# WaterLevel.net
KiCad netlist of a schematic drawn in EAGLE
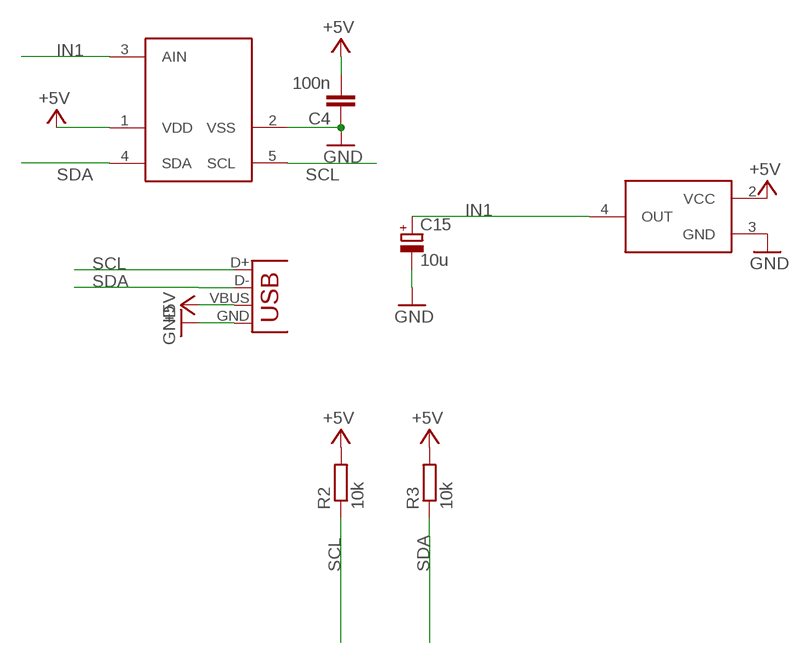
[diagram p0: schematic, sheet 1]

(export (version "E")
  (design (tool "Eeschema 10.0.6"))
  (components
    (comp (ref "C4")
      (value "100n")
      (footprint "eagle-import:C0805K")
      (libsource (lib "eagle-import") (part "C-EUC0805K"))
    )
    (comp (ref "C15")
      (value "10u")
      (footprint "eagle-import:A_3216-18W")
      (libsource (lib "eagle-import") (part "CPOL-EUA/3216-18W"))
    )
    (comp (ref "IC1")
      (value "MPVZ5004GW7U")
      (footprint "eagle-import:MPVZ5004GW7U")
      (libsource (lib "eagle-import") (part "MPVZ5004GW7U"))
    )
    (comp (ref "R2")
      (value "10k")
      (footprint "eagle-import:R0805")
      (libsource (lib "eagle-import") (part "R-EU_R0805"))
    )
    (comp (ref "R3")
      (value "10k")
      (footprint "eagle-import:R0805")
      (libsource (lib "eagle-import") (part "R-EU_R0805"))
    )
    (comp (ref "U$2")
      (value "MCP3221A7")
      (footprint "eagle-import:SOT23-5")
      (libsource (lib "eagle-import") (part "MCP3221"))
    )
    (comp (ref "X5")
      (value "USBSMD")
      (footprint "eagle-import:USB-MINIB")
      (libsource (lib "eagle-import") (part "USBSMD"))
    )
  )
  (nets
    (net (code "1") (name "+5V") (class "Default")
      (node (ref "C4") (pin "2") (pinfunction "2_2") (pintype "passive"))
      (node (ref "IC1") (pin "2") (pinfunction "VCC_2") (pintype "bidirectional"))
      (node (ref "R2") (pin "2") (pinfunction "2_2") (pintype "passive"))
      (node (ref "R3") (pin "2") (pinfunction "2_2") (pintype "passive"))
      (node (ref "U$2") (pin "1") (pinfunction "VDD_1") (pintype "bidirectional"))
      (node (ref "X5") (pin "VBUS") (pinfunction "VBUS_VBUS") (pintype "bidirectional"))
    )
    (net (code "2") (name "/IN1") (class "Default")
      (node (ref "C15") (pin "+") (pinfunction "+_+") (pintype "passive"))
      (node (ref "IC1") (pin "4") (pinfunction "OUT_4") (pintype "bidirectional"))
      (node (ref "U$2") (pin "3") (pinfunction "AIN_3") (pintype "bidirectional"))
    )
    (net (code "3") (name "/SCL") (class "Default")
      (node (ref "R2") (pin "1") (pinfunction "1_1") (pintype "passive"))
      (node (ref "U$2") (pin "5") (pinfunction "SCL_5") (pintype "bidirectional"))
      (node (ref "X5") (pin "D+") (pinfunction "D+_D+") (pintype "bidirectional"))
    )
    (net (code "4") (name "/SDA") (class "Default")
      (node (ref "R3") (pin "1") (pinfunction "1_1") (pintype "passive"))
      (node (ref "U$2") (pin "4") (pinfunction "SDA_4") (pintype "bidirectional"))
      (node (ref "X5") (pin "D-") (pinfunction "D-_D-") (pintype "bidirectional"))
    )
    (net (code "5") (name "GND") (class "Default")
      (node (ref "C15") (pin "-") (pinfunction "-_-") (pintype "passive"))
      (node (ref "C4") (pin "1") (pinfunction "1_1") (pintype "passive"))
      (node (ref "IC1") (pin "3") (pinfunction "GND_3") (pintype "bidirectional"))
      (node (ref "U$2") (pin "2") (pinfunction "VSS_2") (pintype "bidirectional"))
      (node (ref "X5") (pin "GND") (pinfunction "GND_GND") (pintype "bidirectional"))
    )
  )
)
